# CONTROLADOR_MAX31865_RELE.net
KiCad netlist of a schematic drawn in EAGLE
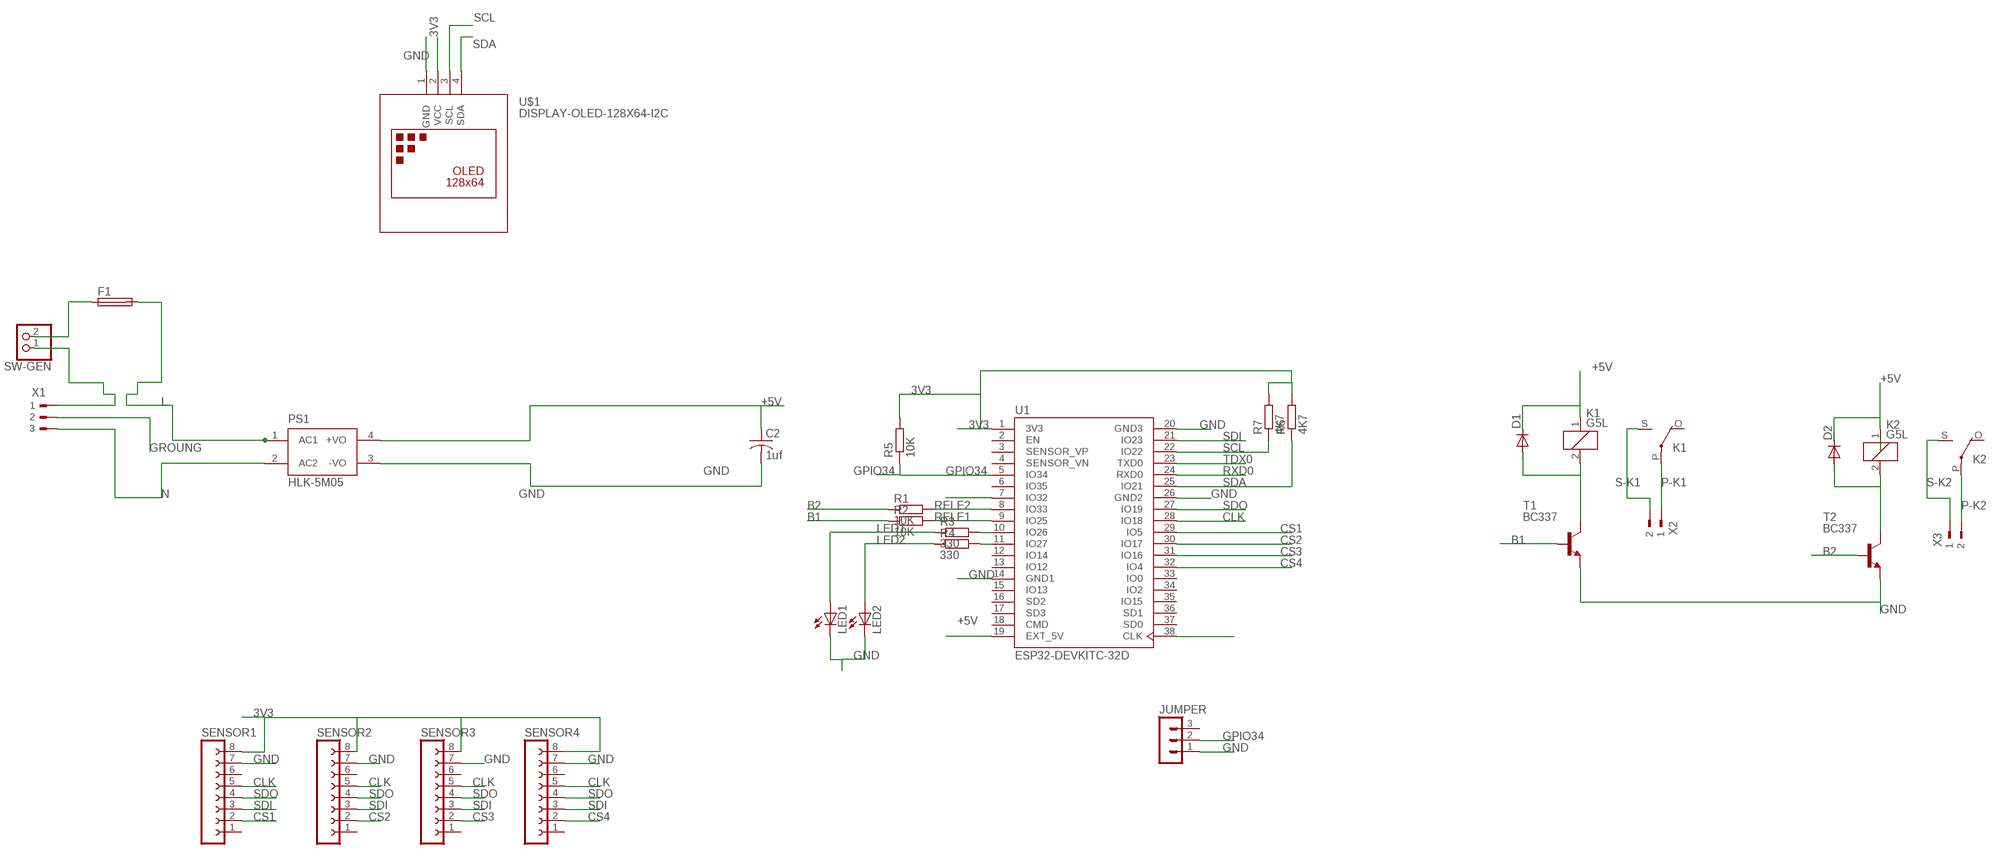
[diagram p0: schematic, sheet 1]

(export (version "E")
  (design (tool "Eeschema 10.0.6"))
  (components
    (comp (ref "C2")
      (value "1uf")
      (footprint "eagle-import:C1206")
      (libsource (lib "eagle-import") (part "C-USC1206"))
    )
    (comp (ref "D1")
      (value "DIODE-DO214AC")
      (footprint "eagle-import:DO214AC")
      (libsource (lib "eagle-import") (part "DIODE-DO214AC"))
    )
    (comp (ref "D2")
      (value "DIODE-DO214AC")
      (footprint "eagle-import:DO214AC")
      (libsource (lib "eagle-import") (part "DIODE-DO214AC"))
    )
    (comp (ref "F1")
      (value "SH22,5A")
      (footprint "eagle-import:SH22,5A")
      (fields (field (name "MPN") "0031.7701.11"))
      (libsource (lib "eagle-import") (part "SH22,5A"))
    )
    (comp (ref "JUMPER")
      (value "MA03-1")
      (footprint "eagle-import:MA03-1")
      (libsource (lib "eagle-import") (part "MA03-1"))
    )
    (comp (ref "K1")
      (value "G5L")
      (footprint "eagle-import:G5LE")
      (libsource (lib "eagle-import") (part "G5L"))
    )
    (comp (ref "K2")
      (value "G5L")
      (footprint "eagle-import:G5LE")
      (libsource (lib "eagle-import") (part "G5L"))
    )
    (comp (ref "LED1")
      (value "LED3MM")
      (footprint "eagle-import:LED3MM")
      (libsource (lib "eagle-import") (part "LED3MM"))
    )
    (comp (ref "LED2")
      (value "LED3MM")
      (footprint "eagle-import:LED3MM")
      (libsource (lib "eagle-import") (part "LED3MM"))
    )
    (comp (ref "PS1")
      (value "HLK-5M05")
      (footprint "eagle-import:CONV_HLK-5M05")
      (fields (field (name "MF") "Hi-link"))
      (libsource (lib "eagle-import") (part "HLK-5M05"))
    )
    (comp (ref "R1")
      (value "10K")
      (footprint "eagle-import:M1206")
      (libsource (lib "eagle-import") (part "R-EU_M1206"))
    )
    (comp (ref "R2")
      (value "10K")
      (footprint "eagle-import:M1206")
      (libsource (lib "eagle-import") (part "R-EU_M1206"))
    )
    (comp (ref "R3")
      (value "330")
      (footprint "eagle-import:M1206")
      (libsource (lib "eagle-import") (part "R-EU_M1206"))
    )
    (comp (ref "R4")
      (value "330")
      (footprint "eagle-import:M1206")
      (libsource (lib "eagle-import") (part "R-EU_M1206"))
    )
    (comp (ref "R5")
      (value "10K")
      (footprint "eagle-import:M1206")
      (libsource (lib "eagle-import") (part "R-EU_M1206"))
    )
    (comp (ref "R6")
      (value "4K7")
      (footprint "eagle-import:M1206")
      (libsource (lib "eagle-import") (part "R-EU_M1206"))
    )
    (comp (ref "R7")
      (value "4K7")
      (footprint "eagle-import:M1206")
      (libsource (lib "eagle-import") (part "R-EU_M1206"))
    )
    (comp (ref "SENSOR1")
      (value "FE08-1")
      (footprint "eagle-import:FE08")
      (libsource (lib "eagle-import") (part "FE08-1"))
    )
    (comp (ref "SENSOR2")
      (value "FE08-1")
      (footprint "eagle-import:FE08")
      (libsource (lib "eagle-import") (part "FE08-1"))
    )
    (comp (ref "SENSOR3")
      (value "FE08-1")
      (footprint "eagle-import:FE08")
      (libsource (lib "eagle-import") (part "FE08-1"))
    )
    (comp (ref "SENSOR4")
      (value "FE08-1")
      (footprint "eagle-import:FE08")
      (libsource (lib "eagle-import") (part "FE08-1"))
    )
    (comp (ref "SW-GEN")
      (value "PINHD-1X2")
      (footprint "eagle-import:1X02")
      (libsource (lib "eagle-import") (part "PINHD-1X2"))
    )
    (comp (ref "T1")
      (value "BC337")
      (footprint "eagle-import:TO92")
      (libsource (lib "eagle-import") (part "BC337"))
    )
    (comp (ref "T2")
      (value "BC337")
      (footprint "eagle-import:TO92")
      (libsource (lib "eagle-import") (part "BC337"))
    )
    (comp (ref "U$1")
      (value "DISPLAY-OLED-128X64-I2C")
      (footprint "eagle-import:DISPLAY-OLED-128X64-I2C")
      (libsource (lib "eagle-import") (part "DISPLAY-OLED-128X64-I2C"))
    )
    (comp (ref "U1")
      (value "ESP32-DEVKITC-32D")
      (footprint "eagle-import:MODULE_ESP32-DEVKITC-32D")
      (fields (field (name "MF") "Espressif Systems"))
      (libsource (lib "eagle-import") (part "ESP32-DEVKITC-32D"))
    )
    (comp (ref "X1")
      (value "180G-3")
      (footprint "eagle-import:180G-3")
      (libsource (lib "eagle-import") (part "180G-3"))
    )
    (comp (ref "X2")
      (value "90-2")
      (footprint "eagle-import:90-2")
      (libsource (lib "eagle-import") (part "90-2"))
    )
    (comp (ref "X3")
      (value "90-2")
      (footprint "eagle-import:90-2")
      (libsource (lib "eagle-import") (part "90-2"))
    )
  )
  (nets
    (net (code "1") (name "/+5V") (class "Default")
      (node (ref "C2") (pin "1") (pinfunction "1_1") (pintype "passive"))
      (node (ref "D1") (pin "C") (pinfunction "C_C") (pintype "passive"))
      (node (ref "D2") (pin "C") (pinfunction "C_C") (pintype "passive"))
      (node (ref "K1") (pin "1") (pinfunction "1_1") (pintype "passive"))
      (node (ref "K2") (pin "1") (pinfunction "1_1") (pintype "passive"))
      (node (ref "PS1") (pin "4") (pinfunction "+VO_4") (pintype "output"))
      (node (ref "U1") (pin "19") (pinfunction "EXT_5V_19") (pintype "power_in"))
    )
    (net (code "2") (name "/3V3") (class "Default")
      (node (ref "R5") (pin "2") (pinfunction "2_2") (pintype "passive"))
      (node (ref "R6") (pin "2") (pinfunction "2_2") (pintype "passive"))
      (node (ref "R7") (pin "2") (pinfunction "2_2") (pintype "passive"))
      (node (ref "SENSOR1") (pin "8") (pinfunction "8_8") (pintype "passive"))
      (node (ref "SENSOR2") (pin "8") (pinfunction "8_8") (pintype "passive"))
      (node (ref "SENSOR3") (pin "8") (pinfunction "8_8") (pintype "passive"))
      (node (ref "SENSOR4") (pin "8") (pinfunction "8_8") (pintype "passive"))
      (node (ref "U$1") (pin "2") (pinfunction "VCC_2") (pintype "power_in"))
      (node (ref "U1") (pin "1") (pinfunction "3V3_1") (pintype "power_in"))
    )
    (net (code "3") (name "/B1") (class "Default")
      (node (ref "R2") (pin "1") (pinfunction "1_1") (pintype "passive"))
      (node (ref "T1") (pin "2") (pinfunction "B_2") (pintype "passive"))
    )
    (net (code "4") (name "/B2") (class "Default")
      (node (ref "R1") (pin "1") (pinfunction "1_1") (pintype "passive"))
      (node (ref "T2") (pin "2") (pinfunction "B_2") (pintype "passive"))
    )
    (net (code "5") (name "/CLK") (class "Default")
      (node (ref "SENSOR1") (pin "5") (pinfunction "5_5") (pintype "passive"))
      (node (ref "SENSOR2") (pin "5") (pinfunction "5_5") (pintype "passive"))
      (node (ref "SENSOR3") (pin "5") (pinfunction "5_5") (pintype "passive"))
      (node (ref "SENSOR4") (pin "5") (pinfunction "5_5") (pintype "passive"))
      (node (ref "U1") (pin "28") (pinfunction "IO18_28") (pintype "bidirectional"))
    )
    (net (code "6") (name "/CS1") (class "Default")
      (node (ref "SENSOR1") (pin "2") (pinfunction "2_2") (pintype "passive"))
      (node (ref "U1") (pin "29") (pinfunction "IO5_29") (pintype "bidirectional"))
    )
    (net (code "7") (name "/CS2") (class "Default")
      (node (ref "SENSOR2") (pin "2") (pinfunction "2_2") (pintype "passive"))
      (node (ref "U1") (pin "30") (pinfunction "IO17_30") (pintype "bidirectional"))
    )
    (net (code "8") (name "/CS3") (class "Default")
      (node (ref "SENSOR3") (pin "2") (pinfunction "2_2") (pintype "passive"))
      (node (ref "U1") (pin "31") (pinfunction "IO16_31") (pintype "bidirectional"))
    )
    (net (code "9") (name "/CS4") (class "Default")
      (node (ref "SENSOR4") (pin "2") (pinfunction "2_2") (pintype "passive"))
      (node (ref "U1") (pin "32") (pinfunction "IO4_32") (pintype "bidirectional"))
    )
    (net (code "10") (name "/GND") (class "Default")
      (node (ref "C2") (pin "2") (pinfunction "2_2") (pintype "passive"))
      (node (ref "JUMPER") (pin "1") (pinfunction "1_1") (pintype "passive"))
      (node (ref "LED1") (pin "K") (pinfunction "C_K") (pintype "passive"))
      (node (ref "LED2") (pin "K") (pinfunction "C_K") (pintype "passive"))
      (node (ref "PS1") (pin "3") (pinfunction "-VO_3") (pintype "output"))
      (node (ref "SENSOR1") (pin "7") (pinfunction "7_7") (pintype "passive"))
      (node (ref "SENSOR2") (pin "7") (pinfunction "7_7") (pintype "passive"))
      (node (ref "SENSOR3") (pin "7") (pinfunction "7_7") (pintype "passive"))
      (node (ref "SENSOR4") (pin "7") (pinfunction "7_7") (pintype "passive"))
      (node (ref "T1") (pin "1") (pinfunction "E_1") (pintype "passive"))
      (node (ref "T2") (pin "1") (pinfunction "E_1") (pintype "passive"))
      (node (ref "U$1") (pin "1") (pinfunction "GND_1") (pintype "power_in"))
      (node (ref "U1") (pin "14") (pinfunction "GND1_14") (pintype "power_in"))
      (node (ref "U1") (pin "20") (pinfunction "GND3_20") (pintype "power_in"))
      (node (ref "U1") (pin "26") (pinfunction "GND2_26") (pintype "power_in"))
    )
    (net (code "11") (name "/GPIO34") (class "Default")
      (node (ref "JUMPER") (pin "2") (pinfunction "2_2") (pintype "passive"))
      (node (ref "R5") (pin "1") (pinfunction "1_1") (pintype "passive"))
      (node (ref "U1") (pin "5") (pinfunction "IO34_5") (pintype "bidirectional"))
    )
    (net (code "12") (name "/GROUNG") (class "Default")
      (node (ref "X1") (pin "2") (pinfunction "2_2") (pintype "passive"))
    )
    (net (code "13") (name "/L") (class "Default")
      (node (ref "F1") (pin "2") (pinfunction "2_2") (pintype "passive"))
      (node (ref "PS1") (pin "1") (pinfunction "AC1_1") (pintype "input"))
    )
    (net (code "14") (name "/LED1") (class "Default")
      (node (ref "LED1") (pin "A") (pinfunction "A_A") (pintype "passive"))
      (node (ref "R3") (pin "1") (pinfunction "1_1") (pintype "passive"))
    )
    (net (code "15") (name "/LED2") (class "Default")
      (node (ref "LED2") (pin "A") (pinfunction "A_A") (pintype "passive"))
      (node (ref "R4") (pin "1") (pinfunction "1_1") (pintype "passive"))
    )
    (net (code "16") (name "/N") (class "Default")
      (node (ref "PS1") (pin "2") (pinfunction "AC2_2") (pintype "input"))
      (node (ref "X1") (pin "3") (pinfunction "3_3") (pintype "passive"))
    )
    (net (code "17") (name "/P-K1") (class "Default")
      (node (ref "K1") (pin "P") (pinfunction "P_P") (pintype "passive"))
      (node (ref "X2") (pin "1") (pinfunction "1_1") (pintype "passive"))
    )
    (net (code "18") (name "/P-K2") (class "Default")
      (node (ref "K2") (pin "P") (pinfunction "P_P") (pintype "passive"))
      (node (ref "X3") (pin "2") (pinfunction "2_2") (pintype "passive"))
    )
    (net (code "19") (name "/RELE1") (class "Default")
      (node (ref "R2") (pin "2") (pinfunction "2_2") (pintype "passive"))
      (node (ref "U1") (pin "9") (pinfunction "IO25_9") (pintype "bidirectional"))
    )
    (net (code "20") (name "/RELE2") (class "Default")
      (node (ref "R1") (pin "2") (pinfunction "2_2") (pintype "passive"))
      (node (ref "U1") (pin "8") (pinfunction "IO33_8") (pintype "bidirectional"))
    )
    (net (code "21") (name "/RXD0") (class "Default")
      (node (ref "U1") (pin "24") (pinfunction "RXD0_24") (pintype "input"))
    )
    (net (code "22") (name "/S-K1") (class "Default")
      (node (ref "K1") (pin "S") (pinfunction "S_S") (pintype "passive"))
      (node (ref "X2") (pin "2") (pinfunction "2_2") (pintype "passive"))
    )
    (net (code "23") (name "/S-K2") (class "Default")
      (node (ref "K2") (pin "S") (pinfunction "S_S") (pintype "passive"))
      (node (ref "X3") (pin "1") (pinfunction "1_1") (pintype "passive"))
    )
    (net (code "24") (name "/SCL") (class "Default")
      (node (ref "R7") (pin "1") (pinfunction "1_1") (pintype "passive"))
      (node (ref "U$1") (pin "3") (pinfunction "SCL_3") (pintype "bidirectional"))
      (node (ref "U1") (pin "22") (pinfunction "IO22_22") (pintype "bidirectional"))
    )
    (net (code "25") (name "/SDA") (class "Default")
      (node (ref "R6") (pin "1") (pinfunction "1_1") (pintype "passive"))
      (node (ref "U$1") (pin "4") (pinfunction "SDA_4") (pintype "bidirectional"))
      (node (ref "U1") (pin "25") (pinfunction "IO21_25") (pintype "bidirectional"))
    )
    (net (code "26") (name "/SDI") (class "Default")
      (node (ref "SENSOR1") (pin "3") (pinfunction "3_3") (pintype "passive"))
      (node (ref "SENSOR2") (pin "3") (pinfunction "3_3") (pintype "passive"))
      (node (ref "SENSOR3") (pin "3") (pinfunction "3_3") (pintype "passive"))
      (node (ref "SENSOR4") (pin "3") (pinfunction "3_3") (pintype "passive"))
      (node (ref "U1") (pin "21") (pinfunction "IO23_21") (pintype "bidirectional"))
    )
    (net (code "27") (name "/SDO") (class "Default")
      (node (ref "SENSOR1") (pin "4") (pinfunction "4_4") (pintype "passive"))
      (node (ref "SENSOR2") (pin "4") (pinfunction "4_4") (pintype "passive"))
      (node (ref "SENSOR3") (pin "4") (pinfunction "4_4") (pintype "passive"))
      (node (ref "SENSOR4") (pin "4") (pinfunction "4_4") (pintype "passive"))
      (node (ref "U1") (pin "27") (pinfunction "IO19_27") (pintype "bidirectional"))
    )
    (net (code "28") (name "/TDX0") (class "Default")
      (node (ref "U1") (pin "23") (pinfunction "TXD0_23") (pintype "output"))
    )
    (net (code "29") (name "Net-(F1-Pad1)") (class "Default")
      (node (ref "F1") (pin "1") (pinfunction "1_1") (pintype "passive"))
      (node (ref "SW-GEN") (pin "2") (pinfunction "2_2") (pintype "passive"))
    )
    (net (code "30") (name "Net-(SW-GEN-Pad1)") (class "Default")
      (node (ref "SW-GEN") (pin "1") (pinfunction "1_1") (pintype "passive"))
      (node (ref "X1") (pin "1") (pinfunction "1_1") (pintype "passive"))
    )
    (net (code "31") (name "Net-(T1-C)") (class "Default")
      (node (ref "D1") (pin "A") (pinfunction "A_A") (pintype "passive"))
      (node (ref "K1") (pin "2") (pinfunction "2_2") (pintype "passive"))
      (node (ref "T1") (pin "3") (pinfunction "C_3") (pintype "passive"))
    )
    (net (code "32") (name "Net-(T2-C)") (class "Default")
      (node (ref "D2") (pin "A") (pinfunction "A_A") (pintype "passive"))
      (node (ref "K2") (pin "2") (pinfunction "2_2") (pintype "passive"))
      (node (ref "T2") (pin "3") (pinfunction "C_3") (pintype "passive"))
    )
    (net (code "33") (name "Net-(U1-IO26)") (class "Default")
      (node (ref "R3") (pin "2") (pinfunction "2_2") (pintype "passive"))
      (node (ref "U1") (pin "10") (pinfunction "IO26_10") (pintype "bidirectional"))
    )
    (net (code "34") (name "Net-(U1-IO27)") (class "Default")
      (node (ref "R4") (pin "2") (pinfunction "2_2") (pintype "passive"))
      (node (ref "U1") (pin "11") (pinfunction "IO27_11") (pintype "bidirectional"))
    )
    (net (code "35") (name "unconnected-(JUMPER-Pad3)") (class "Default")
      (node (ref "JUMPER") (pin "3") (pinfunction "3_3") (pintype "passive"))
    )
    (net (code "36") (name "unconnected-(K1-PadO)") (class "Default")
      (node (ref "K1") (pin "O") (pinfunction "O_O") (pintype "passive"))
    )
    (net (code "37") (name "unconnected-(K2-PadO)") (class "Default")
      (node (ref "K2") (pin "O") (pinfunction "O_O") (pintype "passive"))
    )
    (net (code "38") (name "unconnected-(SENSOR1-Pad1)") (class "Default")
      (node (ref "SENSOR1") (pin "1") (pinfunction "1_1") (pintype "passive"))
    )
    (net (code "39") (name "unconnected-(SENSOR1-Pad6)") (class "Default")
      (node (ref "SENSOR1") (pin "6") (pinfunction "6_6") (pintype "passive"))
    )
    (net (code "40") (name "unconnected-(SENSOR2-Pad1)") (class "Default")
      (node (ref "SENSOR2") (pin "1") (pinfunction "1_1") (pintype "passive"))
    )
    (net (code "41") (name "unconnected-(SENSOR2-Pad6)") (class "Default")
      (node (ref "SENSOR2") (pin "6") (pinfunction "6_6") (pintype "passive"))
    )
    (net (code "42") (name "unconnected-(SENSOR3-Pad1)") (class "Default")
      (node (ref "SENSOR3") (pin "1") (pinfunction "1_1") (pintype "passive"))
    )
    (net (code "43") (name "unconnected-(SENSOR3-Pad6)") (class "Default")
      (node (ref "SENSOR3") (pin "6") (pinfunction "6_6") (pintype "passive"))
    )
    (net (code "44") (name "unconnected-(SENSOR4-Pad1)") (class "Default")
      (node (ref "SENSOR4") (pin "1") (pinfunction "1_1") (pintype "passive"))
    )
    (net (code "45") (name "unconnected-(SENSOR4-Pad6)") (class "Default")
      (node (ref "SENSOR4") (pin "6") (pinfunction "6_6") (pintype "passive"))
    )
    (net (code "46") (name "unconnected-(U1-CLK-Pad38)") (class "Default")
      (node (ref "U1") (pin "38") (pinfunction "CLK_38") (pintype "input"))
    )
    (net (code "47") (name "unconnected-(U1-CMD-Pad18)") (class "Default")
      (node (ref "U1") (pin "18") (pinfunction "CMD_18") (pintype "bidirectional"))
    )
    (net (code "48") (name "unconnected-(U1-EN-Pad2)") (class "Default")
      (node (ref "U1") (pin "2") (pinfunction "EN_2") (pintype "input"))
    )
    (net (code "49") (name "unconnected-(U1-IO0-Pad33)") (class "Default")
      (node (ref "U1") (pin "33") (pinfunction "IO0_33") (pintype "bidirectional"))
    )
    (net (code "50") (name "unconnected-(U1-IO2-Pad34)") (class "Default")
      (node (ref "U1") (pin "34") (pinfunction "IO2_34") (pintype "bidirectional"))
    )
    (net (code "51") (name "unconnected-(U1-IO12-Pad13)") (class "Default")
      (node (ref "U1") (pin "13") (pinfunction "IO12_13") (pintype "bidirectional"))
    )
    (net (code "52") (name "unconnected-(U1-IO13-Pad15)") (class "Default")
      (node (ref "U1") (pin "15") (pinfunction "IO13_15") (pintype "bidirectional"))
    )
    (net (code "53") (name "unconnected-(U1-IO14-Pad12)") (class "Default")
      (node (ref "U1") (pin "12") (pinfunction "IO14_12") (pintype "bidirectional"))
    )
    (net (code "54") (name "unconnected-(U1-IO15-Pad35)") (class "Default")
      (node (ref "U1") (pin "35") (pinfunction "IO15_35") (pintype "bidirectional"))
    )
    (net (code "55") (name "unconnected-(U1-IO32-Pad7)") (class "Default")
      (node (ref "U1") (pin "7") (pinfunction "IO32_7") (pintype "bidirectional"))
    )
    (net (code "56") (name "unconnected-(U1-IO35-Pad6)") (class "Default")
      (node (ref "U1") (pin "6") (pinfunction "IO35_6") (pintype "bidirectional"))
    )
    (net (code "57") (name "unconnected-(U1-SD0-Pad37)") (class "Default")
      (node (ref "U1") (pin "37") (pinfunction "SD0_37") (pintype "bidirectional"))
    )
    (net (code "58") (name "unconnected-(U1-SD1-Pad36)") (class "Default")
      (node (ref "U1") (pin "36") (pinfunction "SD1_36") (pintype "bidirectional"))
    )
    (net (code "59") (name "unconnected-(U1-SD2-Pad16)") (class "Default")
      (node (ref "U1") (pin "16") (pinfunction "SD2_16") (pintype "bidirectional"))
    )
    (net (code "60") (name "unconnected-(U1-SD3-Pad17)") (class "Default")
      (node (ref "U1") (pin "17") (pinfunction "SD3_17") (pintype "bidirectional"))
    )
    (net (code "61") (name "unconnected-(U1-SENSOR_VN-Pad4)") (class "Default")
      (node (ref "U1") (pin "4") (pinfunction "SENSOR_VN_4") (pintype "input"))
    )
    (net (code "62") (name "unconnected-(U1-SENSOR_VP-Pad3)") (class "Default")
      (node (ref "U1") (pin "3") (pinfunction "SENSOR_VP_3") (pintype "input"))
    )
  )
)
